# m328p-preproduction.net
KiCad netlist of a schematic drawn in EAGLE
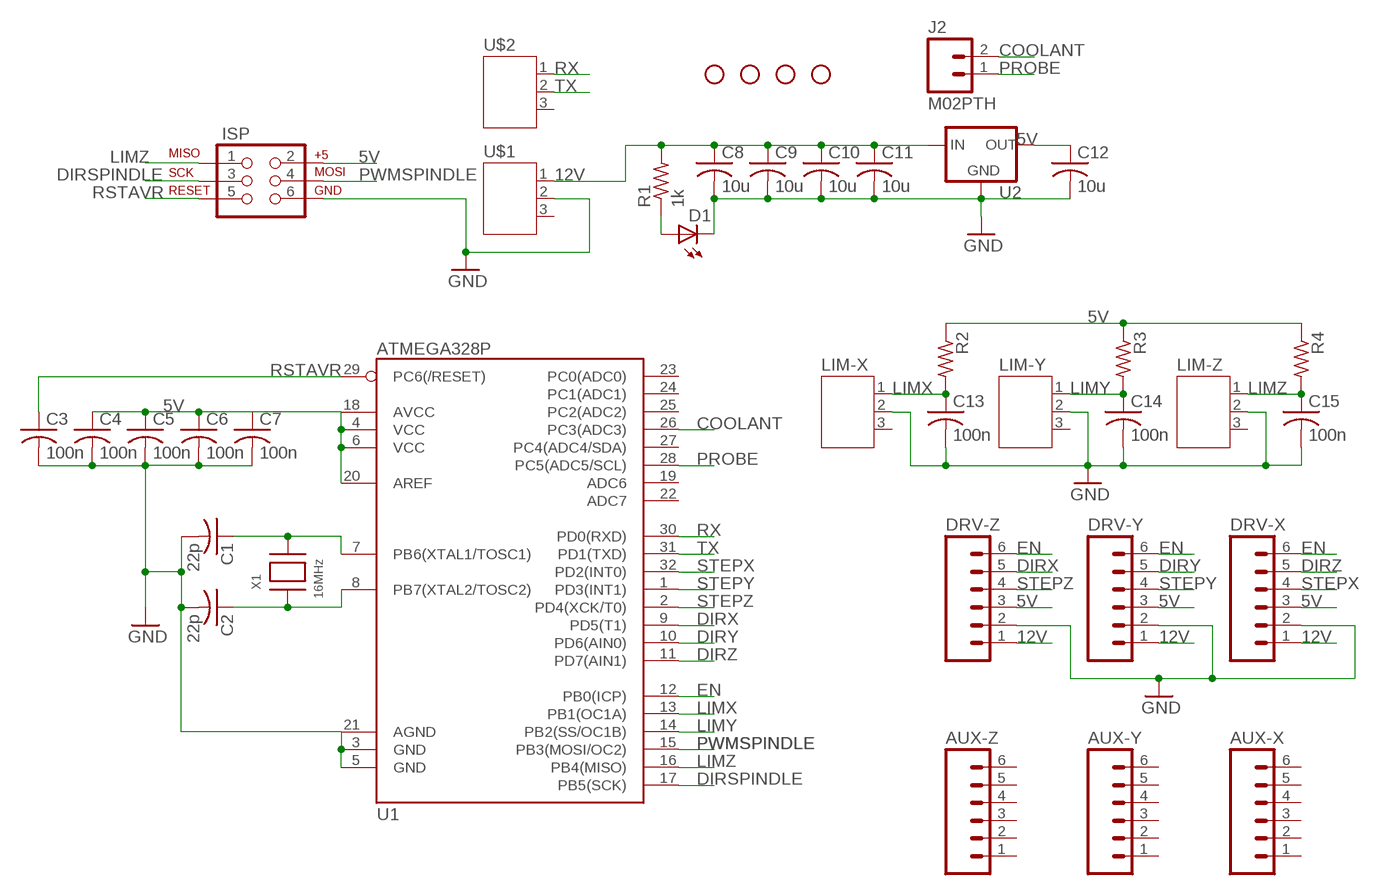
[diagram p0: schematic, sheet 1]

(export (version "E")
  (design (tool "Eeschema 10.0.6"))
  (components
    (comp (ref "AUX-X")
      (value "M06LOCK")
      (footprint "eagle-import:1X06_LOCK")
      (libsource (lib "eagle-import") (part "M06LOCK"))
    )
    (comp (ref "AUX-Y")
      (value "M06LOCK")
      (footprint "eagle-import:1X06_LOCK")
      (libsource (lib "eagle-import") (part "M06LOCK"))
    )
    (comp (ref "AUX-Z")
      (value "M06LOCK")
      (footprint "eagle-import:1X06_LOCK")
      (libsource (lib "eagle-import") (part "M06LOCK"))
    )
    (comp (ref "C1")
      (value "22p")
      (footprint "eagle-import:C0603")
      (libsource (lib "eagle-import") (part "C-USC0603"))
    )
    (comp (ref "C2")
      (value "22p")
      (footprint "eagle-import:C0603")
      (libsource (lib "eagle-import") (part "C-USC0603"))
    )
    (comp (ref "C3")
      (value "100n")
      (footprint "eagle-import:C0603")
      (libsource (lib "eagle-import") (part "C-USC0603"))
    )
    (comp (ref "C4")
      (value "100n")
      (footprint "eagle-import:C0603")
      (libsource (lib "eagle-import") (part "C-USC0603"))
    )
    (comp (ref "C5")
      (value "100n")
      (footprint "eagle-import:C0603")
      (libsource (lib "eagle-import") (part "C-USC0603"))
    )
    (comp (ref "C6")
      (value "100n")
      (footprint "eagle-import:C0603")
      (libsource (lib "eagle-import") (part "C-USC0603"))
    )
    (comp (ref "C7")
      (value "100n")
      (footprint "eagle-import:C0603")
      (libsource (lib "eagle-import") (part "C-USC0603"))
    )
    (comp (ref "C8")
      (value "10u")
      (footprint "eagle-import:C1206")
      (libsource (lib "eagle-import") (part "C-USC1206"))
    )
    (comp (ref "C9")
      (value "10u")
      (footprint "eagle-import:C1206")
      (libsource (lib "eagle-import") (part "C-USC1206"))
    )
    (comp (ref "C10")
      (value "10u")
      (footprint "eagle-import:C1206")
      (libsource (lib "eagle-import") (part "C-USC1206"))
    )
    (comp (ref "C11")
      (value "10u")
      (footprint "eagle-import:C1206")
      (libsource (lib "eagle-import") (part "C-USC1206"))
    )
    (comp (ref "C12")
      (value "10u")
      (footprint "eagle-import:C1206")
      (libsource (lib "eagle-import") (part "C-USC1206"))
    )
    (comp (ref "C13")
      (value "100n")
      (footprint "eagle-import:C0603")
      (libsource (lib "eagle-import") (part "C-USC0603"))
    )
    (comp (ref "C14")
      (value "100n")
      (footprint "eagle-import:C0603")
      (libsource (lib "eagle-import") (part "C-USC0603"))
    )
    (comp (ref "C15")
      (value "100n")
      (footprint "eagle-import:C0603")
      (libsource (lib "eagle-import") (part "C-USC0603"))
    )
    (comp (ref "D1")
      (value "LEDCHIPLED_1206")
      (footprint "eagle-import:CHIPLED_1206")
      (libsource (lib "eagle-import") (part "LEDCHIPLED_1206"))
    )
    (comp (ref "DRV-X")
      (value "M06LOCK")
      (footprint "eagle-import:1X06_LOCK")
      (libsource (lib "eagle-import") (part "M06LOCK"))
    )
    (comp (ref "DRV-Y")
      (value "M06LOCK")
      (footprint "eagle-import:1X06_LOCK")
      (libsource (lib "eagle-import") (part "M06LOCK"))
    )
    (comp (ref "DRV-Z")
      (value "M06LOCK")
      (footprint "eagle-import:1X06_LOCK")
      (libsource (lib "eagle-import") (part "M06LOCK"))
    )
    (comp (ref "ISP")
      (value "AVR_SPI_PRG_6PTH")
      (footprint "eagle-import:2X3")
      (libsource (lib "eagle-import") (part "AVR_SPI_PRG_6PTH"))
    )
    (comp (ref "J2")
      (value "M02PTH")
      (footprint "eagle-import:1X02")
      (libsource (lib "eagle-import") (part "M02PTH"))
    )
    (comp (ref "LIM-X")
      (value "JST-PH3")
      (footprint "eagle-import:JST-PH3")
      (libsource (lib "eagle-import") (part "JST-PH3"))
    )
    (comp (ref "LIM-Y")
      (value "JST-PH3")
      (footprint "eagle-import:JST-PH3")
      (libsource (lib "eagle-import") (part "JST-PH3"))
    )
    (comp (ref "LIM-Z")
      (value "JST-PH3")
      (footprint "eagle-import:JST-PH3")
      (libsource (lib "eagle-import") (part "JST-PH3"))
    )
    (comp (ref "R1")
      (value "1k")
      (footprint "eagle-import:R1206")
      (libsource (lib "eagle-import") (part "R-US_R1206"))
    )
    (comp (ref "R2")
      (value "R-US_R0603")
      (footprint "eagle-import:R0603")
      (libsource (lib "eagle-import") (part "R-US_R0603"))
    )
    (comp (ref "R3")
      (value "R-US_R0603")
      (footprint "eagle-import:R0603")
      (libsource (lib "eagle-import") (part "R-US_R0603"))
    )
    (comp (ref "R4")
      (value "R-US_R0603")
      (footprint "eagle-import:R0603")
      (libsource (lib "eagle-import") (part "R-US_R0603"))
    )
    (comp (ref "STANDOFF1")
      (value "STAND-OFFTIGHT")
      (footprint "eagle-import:STAND-OFF-TIGHT")
      (libsource (lib "eagle-import") (part "STAND-OFFTIGHT"))
    )
    (comp (ref "STANDOFF2")
      (value "STAND-OFFTIGHT")
      (footprint "eagle-import:STAND-OFF-TIGHT")
      (libsource (lib "eagle-import") (part "STAND-OFFTIGHT"))
    )
    (comp (ref "STANDOFF3")
      (value "STAND-OFFTIGHT")
      (footprint "eagle-import:STAND-OFF-TIGHT")
      (libsource (lib "eagle-import") (part "STAND-OFFTIGHT"))
    )
    (comp (ref "STANDOFF4")
      (value "STAND-OFFTIGHT")
      (footprint "eagle-import:STAND-OFF-TIGHT")
      (libsource (lib "eagle-import") (part "STAND-OFFTIGHT"))
    )
    (comp (ref "U$1")
      (value "JST-PH3")
      (footprint "eagle-import:JST-PH3")
      (libsource (lib "eagle-import") (part "JST-PH3"))
    )
    (comp (ref "U$2")
      (value "JST-PH3")
      (footprint "eagle-import:JST-PH3")
      (libsource (lib "eagle-import") (part "JST-PH3"))
    )
    (comp (ref "U1")
      (value "ATMEGA328P")
      (footprint "eagle-import:TQFP32-08")
      (libsource (lib "eagle-import") (part "ATMEGA328_SMT"))
    )
    (comp (ref "U2")
      (value "V_REG_MIC2920")
      (footprint "eagle-import:SOT223")
      (libsource (lib "eagle-import") (part "V_REG_MIC2920"))
    )
    (comp (ref "X1")
      (value "16MHz")
      (footprint "eagle-import:XTAL3215")
      (libsource (lib "eagle-import") (part "XTAL-3.2X1.5"))
    )
  )
  (nets
    (net (code "1") (name "/5V") (class "Default")
      (node (ref "C12") (pin "1") (pinfunction "1_1") (pintype "passive"))
      (node (ref "C4") (pin "1") (pinfunction "1_1") (pintype "passive"))
      (node (ref "C5") (pin "1") (pinfunction "1_1") (pintype "passive"))
      (node (ref "C6") (pin "1") (pinfunction "1_1") (pintype "passive"))
      (node (ref "C7") (pin "1") (pinfunction "1_1") (pintype "passive"))
      (node (ref "DRV-X") (pin "3") (pinfunction "3_3") (pintype "passive"))
      (node (ref "DRV-Y") (pin "3") (pinfunction "3_3") (pintype "passive"))
      (node (ref "DRV-Z") (pin "3") (pinfunction "3_3") (pintype "passive"))
      (node (ref "ISP") (pin "2") (pinfunction "2_2") (pintype "passive"))
      (node (ref "R2") (pin "1") (pinfunction "1_1") (pintype "passive"))
      (node (ref "R3") (pin "1") (pinfunction "1_1") (pintype "passive"))
      (node (ref "R4") (pin "1") (pinfunction "1_1") (pintype "passive"))
      (node (ref "U1") (pin "18") (pinfunction "AVCC_18") (pintype "bidirectional"))
      (node (ref "U1") (pin "20") (pinfunction "AREF_20") (pintype "bidirectional"))
      (node (ref "U1") (pin "4") (pinfunction "VCC_4") (pintype "bidirectional"))
      (node (ref "U1") (pin "6") (pinfunction "VCC_6") (pintype "bidirectional"))
      (node (ref "U2") (pin "3") (pinfunction "OUT_3") (pintype "output"))
    )
    (net (code "2") (name "/12V") (class "Default")
      (node (ref "C10") (pin "1") (pinfunction "1_1") (pintype "passive"))
      (node (ref "C11") (pin "1") (pinfunction "1_1") (pintype "passive"))
      (node (ref "C8") (pin "1") (pinfunction "1_1") (pintype "passive"))
      (node (ref "C9") (pin "1") (pinfunction "1_1") (pintype "passive"))
      (node (ref "DRV-X") (pin "1") (pinfunction "1_1") (pintype "passive"))
      (node (ref "DRV-Y") (pin "1") (pinfunction "1_1") (pintype "passive"))
      (node (ref "DRV-Z") (pin "1") (pinfunction "1_1") (pintype "passive"))
      (node (ref "R1") (pin "2") (pinfunction "2_2") (pintype "passive"))
      (node (ref "U$1") (pin "1") (pinfunction "1_1") (pintype "passive"))
      (node (ref "U2") (pin "1") (pinfunction "IN_1") (pintype "input"))
    )
    (net (code "3") (name "/COOLANT") (class "Default")
      (node (ref "J2") (pin "2") (pinfunction "2_2") (pintype "passive"))
      (node (ref "U1") (pin "26") (pinfunction "PC3(ADC3)_26") (pintype "bidirectional"))
    )
    (net (code "4") (name "/DIRSPINDLE") (class "Default")
      (node (ref "ISP") (pin "3") (pinfunction "3_3") (pintype "passive"))
      (node (ref "U1") (pin "17") (pinfunction "PB5(SCK)_17") (pintype "bidirectional"))
    )
    (net (code "5") (name "/DIRX") (class "Default")
      (node (ref "DRV-Z") (pin "5") (pinfunction "5_5") (pintype "passive"))
      (node (ref "U1") (pin "9") (pinfunction "PD5(T1)_9") (pintype "bidirectional"))
    )
    (net (code "6") (name "/DIRY") (class "Default")
      (node (ref "DRV-Y") (pin "5") (pinfunction "5_5") (pintype "passive"))
      (node (ref "U1") (pin "10") (pinfunction "PD6(AIN0)_10") (pintype "bidirectional"))
    )
    (net (code "7") (name "/DIRZ") (class "Default")
      (node (ref "DRV-X") (pin "5") (pinfunction "5_5") (pintype "passive"))
      (node (ref "U1") (pin "11") (pinfunction "PD7(AIN1)_11") (pintype "bidirectional"))
    )
    (net (code "8") (name "/EN") (class "Default")
      (node (ref "DRV-X") (pin "6") (pinfunction "6_6") (pintype "passive"))
      (node (ref "DRV-Y") (pin "6") (pinfunction "6_6") (pintype "passive"))
      (node (ref "DRV-Z") (pin "6") (pinfunction "6_6") (pintype "passive"))
      (node (ref "U1") (pin "12") (pinfunction "PB0(ICP)_12") (pintype "bidirectional"))
    )
    (net (code "9") (name "/LIMX") (class "Default")
      (node (ref "C13") (pin "1") (pinfunction "1_1") (pintype "passive"))
      (node (ref "LIM-X") (pin "1") (pinfunction "1_1") (pintype "passive"))
      (node (ref "R2") (pin "2") (pinfunction "2_2") (pintype "passive"))
      (node (ref "U1") (pin "13") (pinfunction "PB1(OC1A)_13") (pintype "bidirectional"))
    )
    (net (code "10") (name "/LIMY") (class "Default")
      (node (ref "C14") (pin "1") (pinfunction "1_1") (pintype "passive"))
      (node (ref "LIM-Y") (pin "1") (pinfunction "1_1") (pintype "passive"))
      (node (ref "R3") (pin "2") (pinfunction "2_2") (pintype "passive"))
      (node (ref "U1") (pin "14") (pinfunction "PB2(SS/OC1B)_14") (pintype "bidirectional"))
    )
    (net (code "11") (name "/LIMZ") (class "Default")
      (node (ref "C15") (pin "1") (pinfunction "1_1") (pintype "passive"))
      (node (ref "ISP") (pin "1") (pinfunction "1_1") (pintype "passive"))
      (node (ref "LIM-Z") (pin "1") (pinfunction "1_1") (pintype "passive"))
      (node (ref "R4") (pin "2") (pinfunction "2_2") (pintype "passive"))
      (node (ref "U1") (pin "16") (pinfunction "PB4(MISO)_16") (pintype "bidirectional"))
    )
    (net (code "12") (name "/PROBE") (class "Default")
      (node (ref "J2") (pin "1") (pinfunction "1_1") (pintype "passive"))
      (node (ref "U1") (pin "28") (pinfunction "PC5(ADC5/SCL)_28") (pintype "bidirectional"))
    )
    (net (code "13") (name "/PWMSPINDLE") (class "Default")
      (node (ref "ISP") (pin "4") (pinfunction "4_4") (pintype "passive"))
      (node (ref "U1") (pin "15") (pinfunction "PB3(MOSI/OC2)_15") (pintype "bidirectional"))
    )
    (net (code "14") (name "/RSTAVR") (class "Default")
      (node (ref "C3") (pin "1") (pinfunction "1_1") (pintype "passive"))
      (node (ref "ISP") (pin "5") (pinfunction "5_5") (pintype "passive"))
      (node (ref "U1") (pin "29") (pinfunction "PC6(/RESET)_29") (pintype "bidirectional"))
    )
    (net (code "15") (name "/RX") (class "Default")
      (node (ref "U$2") (pin "1") (pinfunction "1_1") (pintype "passive"))
      (node (ref "U1") (pin "30") (pinfunction "PD0(RXD)_30") (pintype "bidirectional"))
    )
    (net (code "16") (name "/STEPX") (class "Default")
      (node (ref "DRV-X") (pin "4") (pinfunction "4_4") (pintype "passive"))
      (node (ref "U1") (pin "32") (pinfunction "PD2(INT0)_32") (pintype "bidirectional"))
    )
    (net (code "17") (name "/STEPY") (class "Default")
      (node (ref "DRV-Y") (pin "4") (pinfunction "4_4") (pintype "passive"))
      (node (ref "U1") (pin "1") (pinfunction "PD3(INT1)_1") (pintype "bidirectional"))
    )
    (net (code "18") (name "/STEPZ") (class "Default")
      (node (ref "DRV-Z") (pin "4") (pinfunction "4_4") (pintype "passive"))
      (node (ref "U1") (pin "2") (pinfunction "PD4(XCK/T0)_2") (pintype "bidirectional"))
    )
    (net (code "19") (name "/TX") (class "Default")
      (node (ref "U$2") (pin "2") (pinfunction "2_2") (pintype "passive"))
      (node (ref "U1") (pin "31") (pinfunction "PD1(TXD)_31") (pintype "bidirectional"))
    )
    (net (code "20") (name "GND") (class "Default")
      (node (ref "C1") (pin "2") (pinfunction "2_2") (pintype "passive"))
      (node (ref "C10") (pin "2") (pinfunction "2_2") (pintype "passive"))
      (node (ref "C11") (pin "2") (pinfunction "2_2") (pintype "passive"))
      (node (ref "C12") (pin "2") (pinfunction "2_2") (pintype "passive"))
      (node (ref "C13") (pin "2") (pinfunction "2_2") (pintype "passive"))
      (node (ref "C14") (pin "2") (pinfunction "2_2") (pintype "passive"))
      (node (ref "C15") (pin "2") (pinfunction "2_2") (pintype "passive"))
      (node (ref "C2") (pin "2") (pinfunction "2_2") (pintype "passive"))
      (node (ref "C3") (pin "2") (pinfunction "2_2") (pintype "passive"))
      (node (ref "C4") (pin "2") (pinfunction "2_2") (pintype "passive"))
      (node (ref "C5") (pin "2") (pinfunction "2_2") (pintype "passive"))
      (node (ref "C6") (pin "2") (pinfunction "2_2") (pintype "passive"))
      (node (ref "C7") (pin "2") (pinfunction "2_2") (pintype "passive"))
      (node (ref "C8") (pin "2") (pinfunction "2_2") (pintype "passive"))
      (node (ref "C9") (pin "2") (pinfunction "2_2") (pintype "passive"))
      (node (ref "D1") (pin "C") (pinfunction "C_C") (pintype "passive"))
      (node (ref "DRV-X") (pin "2") (pinfunction "2_2") (pintype "passive"))
      (node (ref "DRV-Y") (pin "2") (pinfunction "2_2") (pintype "passive"))
      (node (ref "DRV-Z") (pin "2") (pinfunction "2_2") (pintype "passive"))
      (node (ref "ISP") (pin "6") (pinfunction "6_6") (pintype "passive"))
      (node (ref "LIM-X") (pin "2") (pinfunction "2_2") (pintype "passive"))
      (node (ref "LIM-Y") (pin "2") (pinfunction "2_2") (pintype "passive"))
      (node (ref "LIM-Z") (pin "2") (pinfunction "2_2") (pintype "passive"))
      (node (ref "U$1") (pin "2") (pinfunction "2_2") (pintype "passive"))
      (node (ref "U1") (pin "21") (pinfunction "AGND_21") (pintype "bidirectional"))
      (node (ref "U1") (pin "3") (pinfunction "GND_3") (pintype "bidirectional"))
      (node (ref "U1") (pin "5") (pinfunction "GND_5") (pintype "bidirectional"))
      (node (ref "U2") (pin "2") (pinfunction "GND_2") (pintype "input"))
    )
    (net (code "21") (name "Net-(D1-PadA)") (class "Default")
      (node (ref "D1") (pin "A") (pinfunction "A_A") (pintype "passive"))
      (node (ref "R1") (pin "1") (pinfunction "1_1") (pintype "passive"))
    )
    (net (code "22") (name "Net-(U1-PB6(XTAL1{slash}TOSC1))") (class "Default")
      (node (ref "C1") (pin "1") (pinfunction "1_1") (pintype "passive"))
      (node (ref "U1") (pin "7") (pinfunction "PB6(XTAL1/TOSC1)_7") (pintype "bidirectional"))
      (node (ref "X1") (pin "P$2") (pinfunction "P$2_P$2") (pintype "bidirectional"))
    )
    (net (code "23") (name "Net-(U1-PB7(XTAL2{slash}TOSC2))") (class "Default")
      (node (ref "C2") (pin "1") (pinfunction "1_1") (pintype "passive"))
      (node (ref "U1") (pin "8") (pinfunction "PB7(XTAL2/TOSC2)_8") (pintype "bidirectional"))
      (node (ref "X1") (pin "P$1") (pinfunction "P$1_P$1") (pintype "bidirectional"))
    )
    (net (code "24") (name "unconnected-(AUX-X-Pad1)") (class "Default")
      (node (ref "AUX-X") (pin "1") (pinfunction "1_1") (pintype "passive"))
    )
    (net (code "25") (name "unconnected-(AUX-X-Pad2)") (class "Default")
      (node (ref "AUX-X") (pin "2") (pinfunction "2_2") (pintype "passive"))
    )
    (net (code "26") (name "unconnected-(AUX-X-Pad3)") (class "Default")
      (node (ref "AUX-X") (pin "3") (pinfunction "3_3") (pintype "passive"))
    )
    (net (code "27") (name "unconnected-(AUX-X-Pad4)") (class "Default")
      (node (ref "AUX-X") (pin "4") (pinfunction "4_4") (pintype "passive"))
    )
    (net (code "28") (name "unconnected-(AUX-X-Pad5)") (class "Default")
      (node (ref "AUX-X") (pin "5") (pinfunction "5_5") (pintype "passive"))
    )
    (net (code "29") (name "unconnected-(AUX-X-Pad6)") (class "Default")
      (node (ref "AUX-X") (pin "6") (pinfunction "6_6") (pintype "passive"))
    )
    (net (code "30") (name "unconnected-(AUX-Y-Pad1)") (class "Default")
      (node (ref "AUX-Y") (pin "1") (pinfunction "1_1") (pintype "passive"))
    )
    (net (code "31") (name "unconnected-(AUX-Y-Pad2)") (class "Default")
      (node (ref "AUX-Y") (pin "2") (pinfunction "2_2") (pintype "passive"))
    )
    (net (code "32") (name "unconnected-(AUX-Y-Pad3)") (class "Default")
      (node (ref "AUX-Y") (pin "3") (pinfunction "3_3") (pintype "passive"))
    )
    (net (code "33") (name "unconnected-(AUX-Y-Pad4)") (class "Default")
      (node (ref "AUX-Y") (pin "4") (pinfunction "4_4") (pintype "passive"))
    )
    (net (code "34") (name "unconnected-(AUX-Y-Pad5)") (class "Default")
      (node (ref "AUX-Y") (pin "5") (pinfunction "5_5") (pintype "passive"))
    )
    (net (code "35") (name "unconnected-(AUX-Y-Pad6)") (class "Default")
      (node (ref "AUX-Y") (pin "6") (pinfunction "6_6") (pintype "passive"))
    )
    (net (code "36") (name "unconnected-(AUX-Z-Pad1)") (class "Default")
      (node (ref "AUX-Z") (pin "1") (pinfunction "1_1") (pintype "passive"))
    )
    (net (code "37") (name "unconnected-(AUX-Z-Pad2)") (class "Default")
      (node (ref "AUX-Z") (pin "2") (pinfunction "2_2") (pintype "passive"))
    )
    (net (code "38") (name "unconnected-(AUX-Z-Pad3)") (class "Default")
      (node (ref "AUX-Z") (pin "3") (pinfunction "3_3") (pintype "passive"))
    )
    (net (code "39") (name "unconnected-(AUX-Z-Pad4)") (class "Default")
      (node (ref "AUX-Z") (pin "4") (pinfunction "4_4") (pintype "passive"))
    )
    (net (code "40") (name "unconnected-(AUX-Z-Pad5)") (class "Default")
      (node (ref "AUX-Z") (pin "5") (pinfunction "5_5") (pintype "passive"))
    )
    (net (code "41") (name "unconnected-(AUX-Z-Pad6)") (class "Default")
      (node (ref "AUX-Z") (pin "6") (pinfunction "6_6") (pintype "passive"))
    )
    (net (code "42") (name "unconnected-(LIM-X-Pad3)") (class "Default")
      (node (ref "LIM-X") (pin "3") (pinfunction "3_3") (pintype "passive"))
    )
    (net (code "43") (name "unconnected-(LIM-Y-Pad3)") (class "Default")
      (node (ref "LIM-Y") (pin "3") (pinfunction "3_3") (pintype "passive"))
    )
    (net (code "44") (name "unconnected-(LIM-Z-Pad3)") (class "Default")
      (node (ref "LIM-Z") (pin "3") (pinfunction "3_3") (pintype "passive"))
    )
    (net (code "45") (name "unconnected-(U$1-Pad3)") (class "Default")
      (node (ref "U$1") (pin "3") (pinfunction "3_3") (pintype "passive"))
    )
    (net (code "46") (name "unconnected-(U$2-Pad3)") (class "Default")
      (node (ref "U$2") (pin "3") (pinfunction "3_3") (pintype "passive"))
    )
    (net (code "47") (name "unconnected-(U1-ADC6-Pad19)") (class "Default")
      (node (ref "U1") (pin "19") (pinfunction "ADC6_19") (pintype "bidirectional"))
    )
    (net (code "48") (name "unconnected-(U1-ADC7-Pad22)") (class "Default")
      (node (ref "U1") (pin "22") (pinfunction "ADC7_22") (pintype "bidirectional"))
    )
    (net (code "49") (name "unconnected-(U1-PC0(ADC0)-Pad23)") (class "Default")
      (node (ref "U1") (pin "23") (pinfunction "PC0(ADC0)_23") (pintype "bidirectional"))
    )
    (net (code "50") (name "unconnected-(U1-PC1(ADC1)-Pad24)") (class "Default")
      (node (ref "U1") (pin "24") (pinfunction "PC1(ADC1)_24") (pintype "bidirectional"))
    )
    (net (code "51") (name "unconnected-(U1-PC2(ADC2)-Pad25)") (class "Default")
      (node (ref "U1") (pin "25") (pinfunction "PC2(ADC2)_25") (pintype "bidirectional"))
    )
    (net (code "52") (name "unconnected-(U1-PC4(ADC4{slash}SDA)-Pad27)") (class "Default")
      (node (ref "U1") (pin "27") (pinfunction "PC4(ADC4/SDA)_27") (pintype "bidirectional"))
    )
  )
)
